# AC-Power-Monitor.net
KiCad netlist of a schematic drawn in Altium Designer
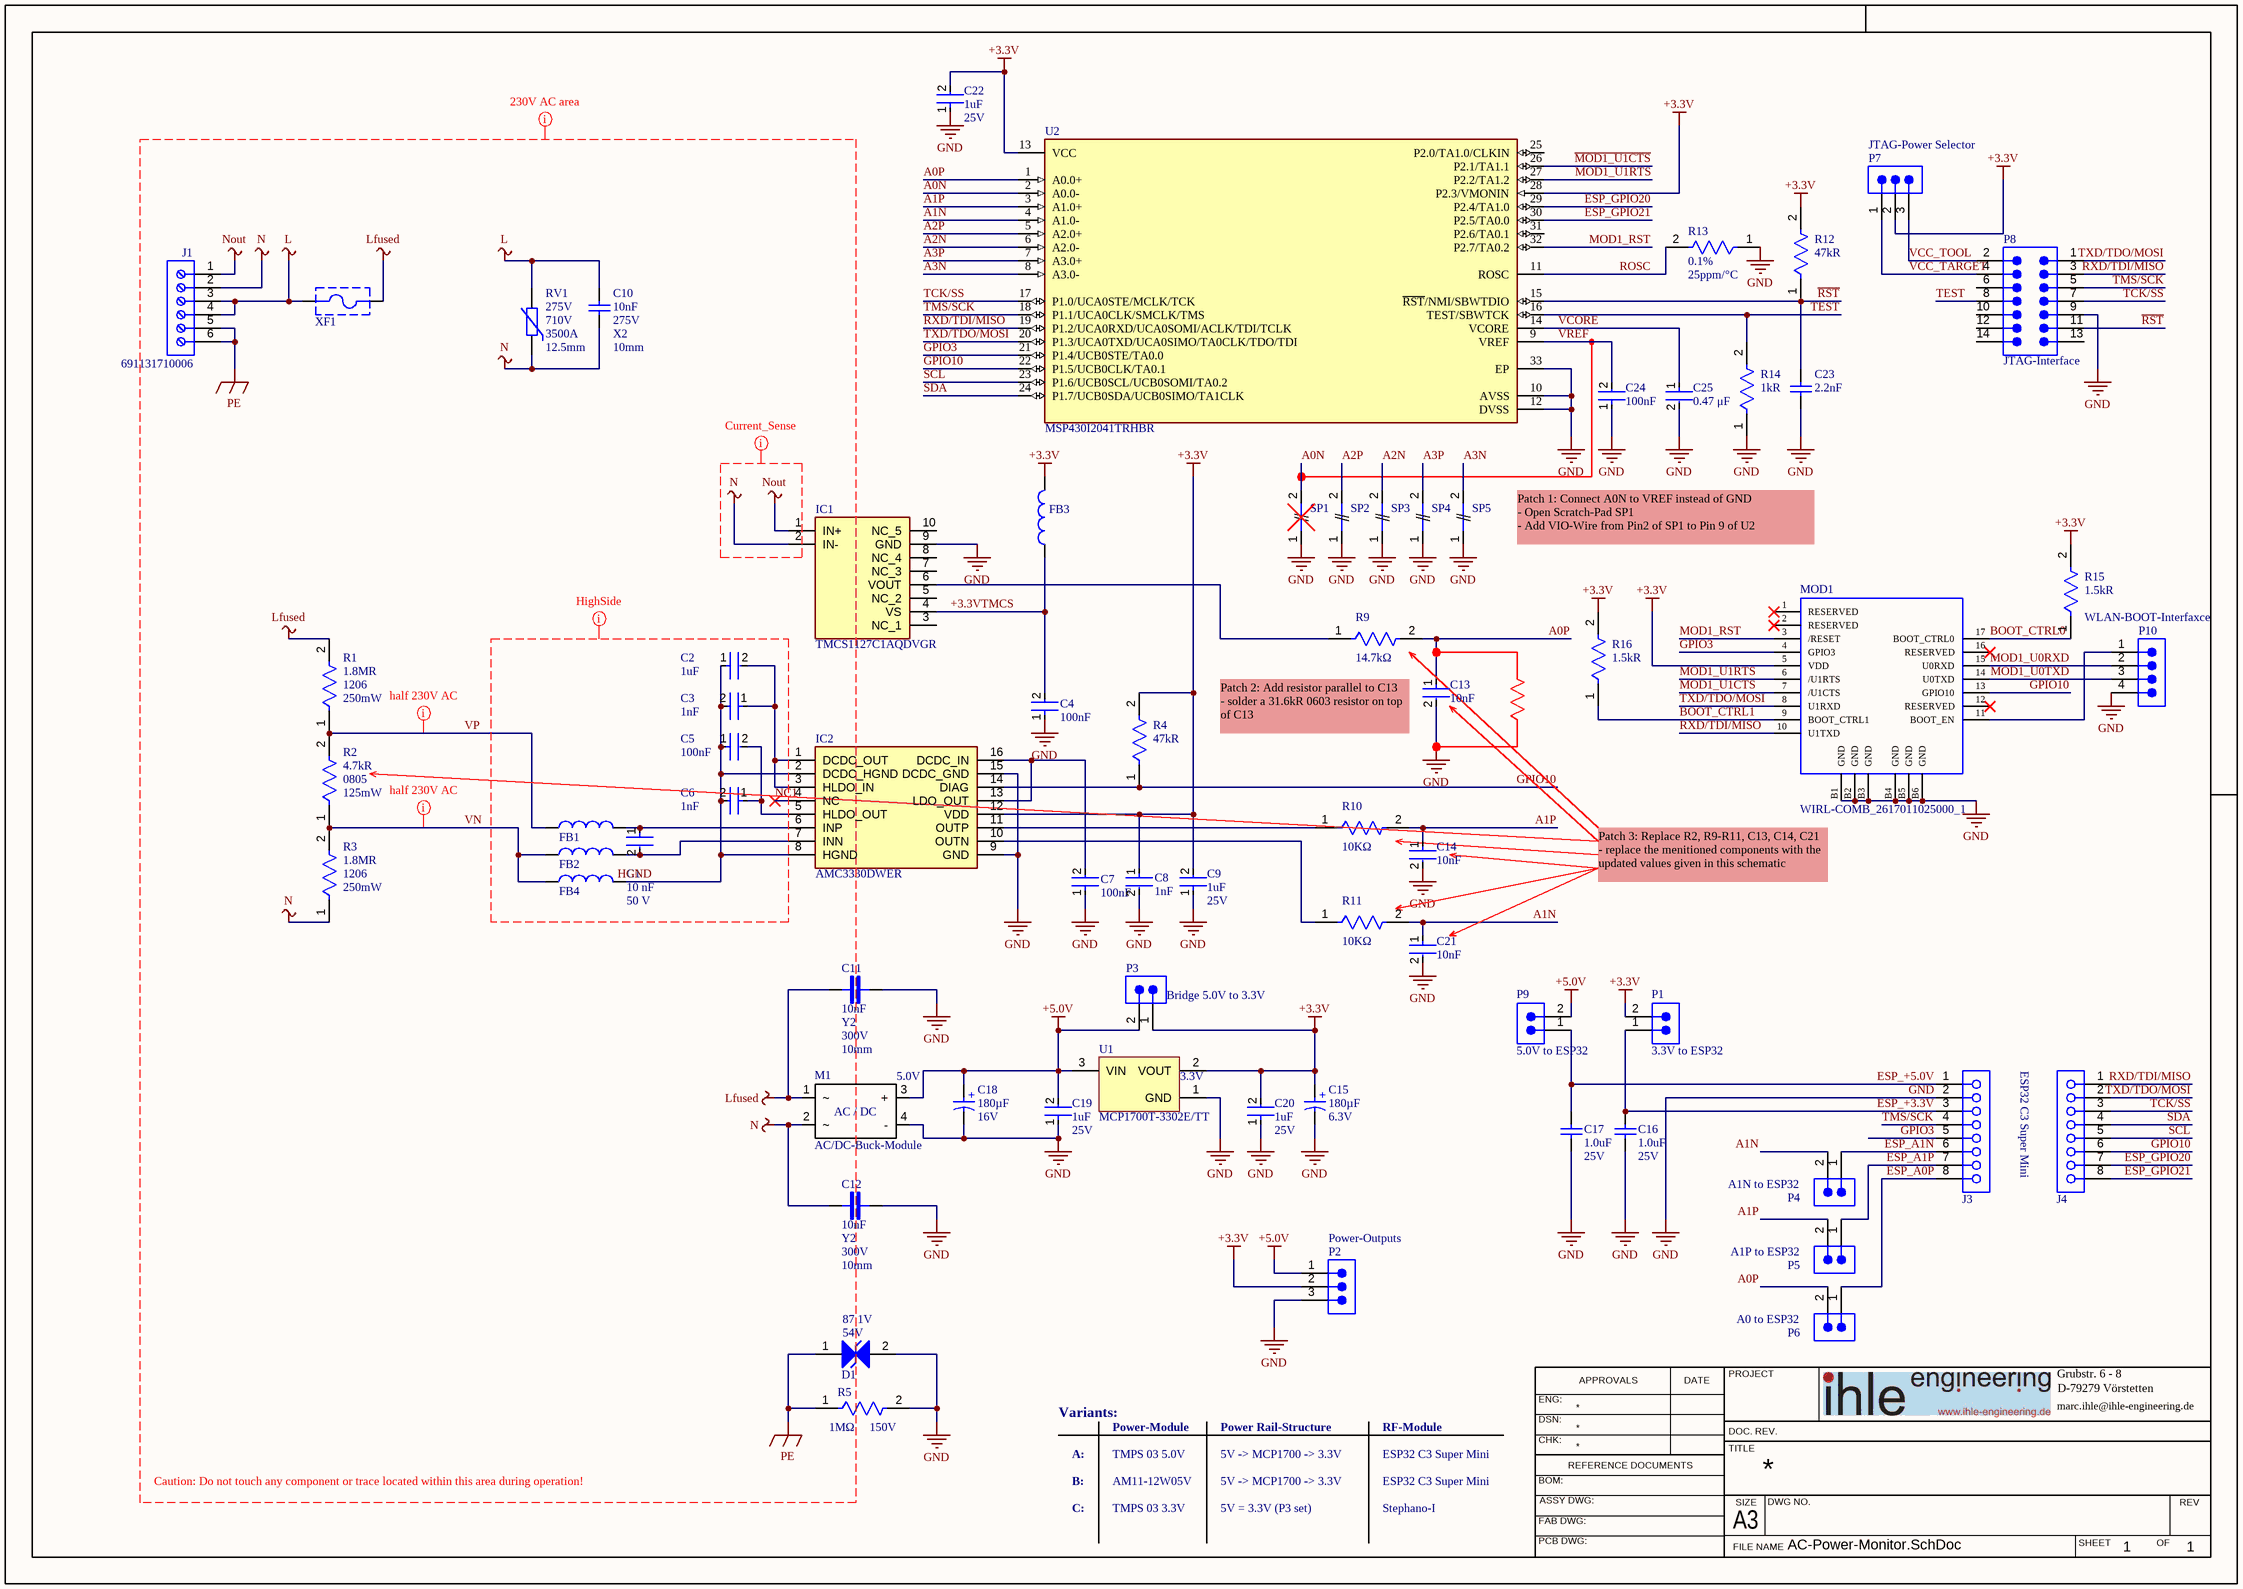
[diagram p0: AC-Power-Monitor.SchDoc]

(export (version "E")
  (design (tool "Eeschema 10.0.6"))
  (components
    (comp (ref "C1")
      (value "10 nF")
      (footprint "FP-CC0603-DA-MFG")
      (description "CAP CER 10000PF 50V X7R 0603")
      (fields
        (field (name "TOLERANCE") "0.1")
        (field (name "VOLTAGE RATING") "50 V")
        (field (name "MANUFACTURER PART NUMBER") "CC0603KRX7R9BB103")
      )
      (libsource (lib "Altium Content Vault") (part "11868f565c42a9108669ba33697ecf6"))
    )
    (comp (ref "C2")
      (value "CGA3E1X7R1E105K080AC")
      (footprint "FP-CGA3E-0_3-0_1-IPC_B")
      (description "Cap Ceramic 1uF 25V X7R 10% Pad SMD 0603 +125°C Automotive T/R")
      (fields
        (field (name "CAPACITANCE") "1uF")
        (field (name "VOLTAGE") "25V")
        (field (name "TOLERANCE") "10%")
      )
      (libsource (lib "Altium Content Vault") (part "b4654b650e69147ec39a6b967a45e02"))
    )
    (comp (ref "C3")
      (value "06035C102KAT2A")
      (footprint "FP-0603-L_1_6_0_15-W_0_81-IPC_B")
      (description "General Purpose Ceramic Capacitor, 0603, 1nF, 10%, X7R, 15%, 50V")
      (fields
        (field (name "CAPACITANCE") "1nF")
        (field (name "VOLTAGE") "50V")
        (field (name "TOLERANCE") "10%")
      )
      (libsource (lib "Altium Content Vault") (part "02cd4be3c70576c341d710602a673aa"))
    )
    (comp (ref "C4")
      (value "CGA3E2X7R1H104K080AA")
      (footprint "FP-CGA3E-0_3-0_1-IPC_A")
      (description "Cap Ceramic 100nF 50V X7R 10% Pad SMD 0603 +125°C Automotive T/R")
      (fields
        (field (name "TOLERANCE") "10%")
        (field (name "CAPACITANCE") "100nF")
        (field (name "VOLTAGE") "50V")
      )
      (libsource (lib "Altium Content Vault") (part "b4654b650e69147ec39a6b967a45e02"))
    )
    (comp (ref "C5")
      (value "CGA3E2X7R1H104K080AA")
      (footprint "FP-CGA3E-0_3-0_1-IPC_C")
      (description "Cap Ceramic 100nF 50V X7R 10% Pad SMD 0603 +125°C Automotive T/R")
      (fields
        (field (name "TOLERANCE") "10%")
        (field (name "CAPACITANCE") "100nF")
        (field (name "VOLTAGE") "50V")
      )
      (libsource (lib "Altium Content Vault") (part "b4654b650e69147ec39a6b967a45e02"))
    )
    (comp (ref "C6")
      (value "06035C102KAT2A")
      (footprint "FP-0603-L_1_6_0_15-W_0_81-IPC_B")
      (description "General Purpose Ceramic Capacitor, 0603, 1nF, 10%, X7R, 15%, 50V")
      (fields
        (field (name "CAPACITANCE") "1nF")
        (field (name "VOLTAGE") "50V")
        (field (name "TOLERANCE") "10%")
      )
      (libsource (lib "Altium Content Vault") (part "02cd4be3c70576c341d710602a673aa"))
    )
    (comp (ref "C7")
      (value "CGA3E2X7R1H104K080AA")
      (footprint "FP-CGA3E-0_3-0_1-IPC_A")
      (description "Cap Ceramic 100nF 50V X7R 10% Pad SMD 0603 +125°C Automotive T/R")
      (fields
        (field (name "TOLERANCE") "10%")
        (field (name "CAPACITANCE") "100nF")
        (field (name "VOLTAGE") "50V")
      )
      (libsource (lib "Altium Content Vault") (part "b4654b650e69147ec39a6b967a45e02"))
    )
    (comp (ref "C8")
      (value "06035C102KAT2A")
      (footprint "FP-0603-L_1_6_0_15-W_0_81-IPC_A")
      (description "General Purpose Ceramic Capacitor, 0603, 1nF, 10%, X7R, 15%, 50V")
      (fields
        (field (name "CAPACITANCE") "1nF")
        (field (name "VOLTAGE") "50V")
        (field (name "TOLERANCE") "10%")
      )
      (libsource (lib "Altium Content Vault") (part "02cd4be3c70576c341d710602a673aa"))
    )
    (comp (ref "C9")
      (value "CGA3E1X7R1E105K080AC")
      (footprint "FP-CGA3E-0_3-0_1-IPC_A")
      (description "Cap Ceramic 1uF 25V X7R 10% Pad SMD 0603 +125°C Automotive T/R")
      (fields
        (field (name "CAPACITANCE") "1uF")
        (field (name "VOLTAGE RATING") "25V")
        (field (name "VOLTAGE") "25V")
        (field (name "TOLERANCE") "10%")
      )
      (libsource (lib "Altium Content Vault") (part "b4654b650e69147ec39a6b967a45e02"))
    )
    (comp (ref "C10")
      (value "10nF")
      (footprint "WCAP-FTX2_L13W5H11_CS")
      (description "WCAP-FTX2 Film Capacitor, THT, L13 x W5 x H11mm, 10nF, 275V")
      (fields
        (field (name "MANUFACTURER PART NUMBER") "890324023006CS")
        (field (name "MANUFACTURER") "Wurth Elektronik")
        (field (name "CAPACITANCE") "10nF")
        (field (name "PITCH") "10mm")
        (field (name "RATED VOLTAGE (AC)") "275V")
        (field (name "SAFTY CLASS") "X2")
      )
      (libsource (lib "Altium_WCAP-FTX2 (rev23a)") (part "890324023006CS"))
    )
    (comp (ref "C11")
      (value "MKY22W21003I00")
      (footprint "MKY22W2")
      (fields
        (field (name "CAPACITANCE") "10nF")
        (field (name "SAFTY CLASS") "Y2")
        (field (name "VOLTAGE (AC)") "300V")
        (field (name "PITCH") "10mm")
      )
      (libsource (lib "Ihle_Components") (part "C_unipolar"))
    )
    (comp (ref "C12")
      (value "MKY22W21003I00")
      (footprint "MKY22W2")
      (fields
        (field (name "CAPACITANCE") "10nF")
        (field (name "SAFTY CLASS") "Y2")
        (field (name "VOLTAGE (AC)") "300V")
        (field (name "PITCH") "10mm")
      )
      (libsource (lib "Ihle_Components") (part "C_unipolar"))
    )
    (comp (ref "C13")
      (value "06035C103KAT4A")
      (footprint "FP-0603-L_1_6_0_15-W_0_81-IPC_B")
      (description "CAP CER 10000PF 50V X7R 0603")
      (fields
        (field (name "TOLERANCE") "10%")
        (field (name "VOLTAGE") "50V")
        (field (name "CAPACITANCE") "10nF")
      )
      (libsource (lib "Altium Content Vault") (part "02cd4be3c70576c341d710602a673aa"))
    )
    (comp (ref "C14")
      (value "06035C103KAT4A")
      (footprint "FP-0603-L_1_6_0_15-W_0_81-IPC_B")
      (description "CAP CER 10000PF 50V X7R 0603")
      (fields
        (field (name "TOLERANCE") "10%")
        (field (name "VOLTAGE") "50V")
        (field (name "CAPACITANCE") "10nF")
      )
      (libsource (lib "Altium Content Vault") (part "02cd4be3c70576c341d710602a673aa"))
    )
    (comp (ref "C15")
      (value "180µF")
      (footprint "WCAP-PSLC_D8H11.7")
      (description "WCAP-PSLC Aluminum Polymer Capacitor, V-Chip SMT, D8 x H11.7mm, 180µF, 6.3V")
      (fields
        (field (name "MANUFACTURER PART NUMBER") "875075155001")
        (field (name "MANUFACTURER") "Wurth Elektronik")
        (field (name "CAPACITANCE") "180µF")
        (field (name "RATED VOLTAGE (DC)") "6.3V")
      )
      (libsource (lib "Altium_WCAP-PSLC (rev22c)(1)") (part "875075155001"))
    )
    (comp (ref "C16")
      (value "C0603C105K3RACTU")
      (footprint "CAPC1608X87X35LL15T15")
      (fields
        (field (name "MANUFACTURER") "Kemet")
        (field (name "CAPACITANCE") "1.0uF")
        (field (name "RATED VOLTAGE") "25V")
      )
      (libsource (lib "Altium Content Vault") (part "CAP"))
    )
    (comp (ref "C17")
      (value "C0603C105K3RACTU")
      (footprint "CAPC1608X87X35LL15T15")
      (fields
        (field (name "MANUFACTURER") "Kemet")
        (field (name "CAPACITANCE") "1.0uF")
        (field (name "RATED VOLTAGE") "25V")
      )
      (libsource (lib "Altium Content Vault") (part "CAP"))
    )
    (comp (ref "C18")
      (value "180µF")
      (footprint "WCAP-PSLC_D8H11.7")
      (description "WCAP-PSLC Aluminum Polymer Capacitor, V-Chip SMT, D8 x H11.7mm, 180µF, 16V")
      (fields
        (field (name "MANUFACTURER PART NUMBER") "875075355001")
        (field (name "MANUFACTURER") "Wurth Elektronik")
        (field (name "CAPACITANCE") "180µF")
        (field (name "RATED VOLTAGE (DC)") "16V")
      )
      (libsource (lib "Altium_WCAP-PSLC (rev22c)(1)") (part "875075355001"))
    )
    (comp (ref "C19")
      (value "CGA3E1X7R1E105K080AC")
      (footprint "FP-CGA3E-0_3-0_1-IPC_A")
      (description "Cap Ceramic 1uF 25V X7R 10% Pad SMD 0603 +125°C Automotive T/R")
      (fields
        (field (name "CAPACITANCE") "1uF")
        (field (name "VOLTAGE RATING") "25V")
        (field (name "VOLTAGE") "25V")
        (field (name "TOLERANCE") "10%")
      )
      (libsource (lib "Altium Content Vault") (part "b4654b650e69147ec39a6b967a45e02"))
    )
    (comp (ref "C20")
      (value "CGA3E1X7R1E105K080AC")
      (footprint "FP-CGA3E-0_3-0_1-IPC_A")
      (description "Cap Ceramic 1uF 25V X7R 10% Pad SMD 0603 +125°C Automotive T/R")
      (fields
        (field (name "CAPACITANCE") "1uF")
        (field (name "VOLTAGE RATING") "25V")
        (field (name "VOLTAGE") "25V")
        (field (name "TOLERANCE") "10%")
      )
      (libsource (lib "Altium Content Vault") (part "b4654b650e69147ec39a6b967a45e02"))
    )
    (comp (ref "C21")
      (value "06035C103KAT4A")
      (footprint "FP-0603-L_1_6_0_15-W_0_81-IPC_B")
      (description "CAP CER 10000PF 50V X7R 0603")
      (fields
        (field (name "TOLERANCE") "10%")
        (field (name "VOLTAGE") "50V")
        (field (name "CAPACITANCE") "10nF")
      )
      (libsource (lib "Altium Content Vault") (part "02cd4be3c70576c341d710602a673aa"))
    )
    (comp (ref "C22")
      (value "CGA3E1X7R1E105K080AC")
      (footprint "FP-CGA3E-0_3-0_1-IPC_B")
      (description "Cap Ceramic 1uF 25V X7R 10% Pad SMD 0603 +125°C Automotive T/R")
      (fields
        (field (name "CAPACITANCE") "1uF")
        (field (name "VOLTAGE RATING") "25V")
        (field (name "VOLTAGE") "25V")
        (field (name "TOLERANCE") "10%")
      )
      (libsource (lib "Altium Content Vault") (part "b4654b650e69147ec39a6b967a45e02"))
    )
    (comp (ref "C23")
      (value "885012206085")
      (footprint "WCAP-CSGP_0603_L1.6W0.8H0.8_Reflow")
      (fields (field (name "CAPACITANCE") "2.2nF") (field (name "TOLERANCE") "10%"))
      (libsource (lib "Altium Content Vault") (part "Capacitor_Non-Polarized"))
    )
    (comp (ref "C24")
      (value "CGA3E2X7R1H104K080AA")
      (footprint "FP-CGA3E-0_3-0_1-IPC_B")
      (description "Cap Ceramic 100nF 50V X7R 10% Pad SMD 0603 +125°C Automotive T/R")
      (fields
        (field (name "TOLERANCE") "10%")
        (field (name "CAPACITANCE") "100nF")
        (field (name "VOLTAGE") "50V")
      )
      (libsource (lib "Altium Content Vault") (part "b4654b650e69147ec39a6b967a45e02"))
    )
    (comp (ref "C25")
      (value "0.47 μF")
      (footprint "FP-C0603C-CF-IPC_B")
      (description "CAP CER 0.47UF 16V X7R 0603")
      (fields (field (name "TOLERANCE") "0.1") (field (name "MANUFACTURER PART NUMBER") "C0603C474K4RACTU"))
      (libsource (lib "Altium Content Vault") (part "b4654b650e69147ec39a6b967a45e02"))
    )
    (comp (ref "D1")
      (value "400W, 54VDC")
      (footprint "WE-TVSP_DO-214AC_Bidirectional")
      (description "WE-TVSP SMT Power TVS Diode, DO-214AC, Bidirectional, 400W, 54VDC")
      (fields
        (field (name "MANUFACTURER PART NUMBER") "824501541")
        (field (name "MANUFACTURER") "Wurth Elektronik")
        (field (name "CLAMPING VOLTAGE") "87.1V")
        (field (name "OPERATING VOLTAGE (DC)") "54V")
      )
      (libsource (lib "Altium_WE-TVSP (rev22b)(1)") (part "824501541"))
    )
    (comp (ref "FB1")
      (value "1800Ohm")
      (footprint "WE-TMSB_0402_HF/HS/WB")
      (description "WE-TMSB Tiny Multilayer Suppression Bead, size 0402, 1800Ohm, 0.21A")
      (fields
        (field (name "MANUFACTURER PART NUMBER") "74269244182")
        (field (name "MANUFACTURER") "Wurth Elektronik")
      )
      (libsource (lib "WE-TMSB (rev24a)") (part "74269244182"))
    )
    (comp (ref "FB2")
      (value "1800Ohm")
      (footprint "WE-TMSB_0402_HF/HS/WB")
      (description "WE-TMSB Tiny Multilayer Suppression Bead, size 0402, 1800Ohm, 0.21A")
      (fields
        (field (name "MANUFACTURER PART NUMBER") "74269244182")
        (field (name "MANUFACTURER") "Wurth Elektronik")
      )
      (libsource (lib "WE-TMSB (rev24a)") (part "74269244182"))
    )
    (comp (ref "FB3")
      (value "1800Ohm")
      (footprint "WE-TMSB_0402_HF/HS/WB")
      (description "WE-TMSB Tiny Multilayer Suppression Bead, size 0402, 1800Ohm, 0.21A")
      (fields
        (field (name "MANUFACTURER PART NUMBER") "74269244182")
        (field (name "MANUFACTURER") "Wurth Elektronik")
      )
      (libsource (lib "WE-TMSB (rev24a)") (part "74269244182"))
    )
    (comp (ref "FB4")
      (value "1800Ohm")
      (footprint "WE-TMSB_0402_HF/HS/WB")
      (description "WE-TMSB Tiny Multilayer Suppression Bead, size 0402, 1800Ohm, 0.21A")
      (fields
        (field (name "MANUFACTURER PART NUMBER") "74269244182")
        (field (name "MANUFACTURER") "Wurth Elektronik")
      )
      (libsource (lib "WE-TMSB (rev24a)") (part "74269244182"))
    )
    (comp (ref "IC1")
      (value "TMCS1127C1AQDVGR")
      (footprint "SamacSys:TMCS1127C1AQDVGR")
      (description "Integrated Circuit")
      (libsource (lib "*") (part "TMCS1127C1AQDVGR"))
    )
    (comp (ref "IC2")
      (value "AMC3330DWER")
      (footprint "SamacSys:SOIC127P1030X265-16N")
      (description "Integrated Circuit")
      (fields (field (name "MOUSER PART NUMBER") "595-AMC3330DWER"))
      (libsource (lib "*") (part "AMC3330DWER"))
    )
    (comp (ref "J1")
      (value "691131710006")
      (footprint "691131710006")
      (description "WR-TBL Series 1317 Horizontal Entry, THT, pitch 5mm, 06p")
      (fields (field (name "MANUFACTURER") "Wurth Elektronik"))
      (libsource (lib "Altium_WR-TBL_Wire Protector (rev25a)") (part "691131710006"))
    )
    (comp (ref "J3")
      (value "61300811821")
      (footprint "61300811821")
      (description "WR-PHD Socket Header, THT, Vertical, pitch 2.54mm, 1 Row, 8P")
      (fields (field (name "MANUFACTURER") "Wurth Elektronik"))
      (libsource (lib "Altium_WR-PHD (rev24a)") (part "61300811821"))
    )
    (comp (ref "J4")
      (value "61300811821")
      (footprint "61300811821")
      (description "WR-PHD Socket Header, THT, Vertical, pitch 2.54mm, 1 Row, 8P")
      (fields (field (name "MANUFACTURER") "Wurth Elektronik"))
      (libsource (lib "Altium_WR-PHD (rev24a)") (part "61300811821"))
    )
    (comp (ref "M1")
      (value "AC/DC-Buck-Module")
      (footprint "TMPS 03")
      (fields (field (name "OUTPUT VOLTAGE") "5.0V"))
      (libsource (lib "Ihle_Components") (part "AC/DC-Buck-Module"))
    )
    (comp (ref "MOD1")
      (value "WIRL-COMB_2617011025000_1")
      (footprint "WE-FP-7")
      (description "Stephano-I - Combined 2.4 GHz Wi-Fi and Bluetooth® LE 5.0 Module")
      (fields (field (name "PART NUMBER") "2617011025000") (field (name "PUBLISHER") "Wurth Elektronik"))
      (libsource (lib "WE_WIRL_Rev17") (part "WIRL-COMB_2617011025000_1"))
    )
    (comp (ref "P1")
      (value "61300211121")
      (footprint "61300211121")
      (description "WR-PHD Pin Header, THT, Vertical, pitch 2.54mm, 1 Row, 2P")
      (fields (field (name "MANUFACTURER") "Wurth Elektronik") (field (name "PURPOSE") "3.3V to ESP32"))
      (libsource (lib "Altium_WR-PHD (rev24a)") (part "61300211121"))
    )
    (comp (ref "P2")
      (value "61300311121")
      (footprint "61300311121")
      (description "WR-PHD Pin Header, THT, Vertical, pitch 2.54mm, 1 Row, 3P")
      (fields (field (name "MANUFACTURER") "Wurth Elektronik") (field (name "PURPOSE") "Power-Outputs"))
      (libsource (lib "Altium_WR-PHD (rev24a)") (part "61300311121"))
    )
    (comp (ref "P3")
      (value "61300211121")
      (footprint "61300211121")
      (description "WR-PHD Pin Header, THT, Vertical, pitch 2.54mm, 1 Row, 2P")
      (fields (field (name "MANUFACTURER") "Wurth Elektronik") (field (name "PURPOSE") "Bridge 5.0V to 3.3V"))
      (libsource (lib "Altium_WR-PHD (rev24a)") (part "61300211121"))
    )
    (comp (ref "P4")
      (value "61300211121")
      (footprint "61300211121")
      (description "WR-PHD Pin Header, THT, Vertical, pitch 2.54mm, 1 Row, 2P")
      (fields (field (name "MANUFACTURER") "Wurth Elektronik") (field (name "PURPOSE") "A1N to ESP32"))
      (libsource (lib "Altium_WR-PHD (rev24a)") (part "61300211121"))
    )
    (comp (ref "P5")
      (value "61300211121")
      (footprint "61300211121")
      (description "WR-PHD Pin Header, THT, Vertical, pitch 2.54mm, 1 Row, 2P")
      (fields (field (name "MANUFACTURER") "Wurth Elektronik") (field (name "PURPOSE") "A1P to ESP32"))
      (libsource (lib "Altium_WR-PHD (rev24a)") (part "61300211121"))
    )
    (comp (ref "P6")
      (value "61300211121")
      (footprint "61300211121")
      (description "WR-PHD Pin Header, THT, Vertical, pitch 2.54mm, 1 Row, 2P")
      (fields (field (name "MANUFACTURER") "Wurth Elektronik") (field (name "PURPOSE") "A0 to ESP32"))
      (libsource (lib "Altium_WR-PHD (rev24a)") (part "61300211121"))
    )
    (comp (ref "P7")
      (value "61300311121")
      (footprint "61300311121")
      (description "WR-PHD Pin Header, THT, Vertical, pitch 2.54mm, 1 Row, 3P")
      (fields (field (name "MANUFACTURER") "Wurth Elektronik") (field (name "PURPOSE") "JTAG-Power Selector"))
      (libsource (lib "Altium_WR-PHD (rev24a)") (part "61300311121"))
    )
    (comp (ref "P8")
      (value "61301421121")
      (footprint "61301421121")
      (description "WR-PHD Pin Header, THT, Vertical, pitch 2.54mm, 2 Row, 14P")
      (fields (field (name "MANUFACTURER") "Wurth Elektronik") (field (name "PURPOSE") "JTAG-Interface"))
      (libsource (lib "Altium_WR-PHD (rev24a)") (part "61301421121"))
    )
    (comp (ref "P9")
      (value "61300211121")
      (footprint "61300211121")
      (description "WR-PHD Pin Header, THT, Vertical, pitch 2.54mm, 1 Row, 2P")
      (fields (field (name "MANUFACTURER") "Wurth Elektronik") (field (name "PURPOSE") "5.0V to ESP32"))
      (libsource (lib "Altium_WR-PHD (rev24a)") (part "61300211121"))
    )
    (comp (ref "P10")
      (value "61300411121")
      (footprint "61300411121")
      (description "WR-PHD Pin Header, THT, Vertical, pitch 2.54mm, 1 Row, 4P")
      (fields
        (field (name "MANUFACTURER") "Wurth Elektronik")
        (field (name "PURPOSE") "WLAN-BOOT-Interfaxce")
      )
      (libsource (lib "Altium_WR-PHD (rev24a)") (part "61300411121"))
    )
    (comp (ref "R1")
      (value "RK73H2BTTD1804F")
      (footprint "FP-RK73H2B-IPC_B")
      (description "1.8MΩ ±1% 0.25W Chip Resistor 1206 Thick Film AEC-Q200 Qualified")
      (fields
        (field (name "POWER RATING") "250mW")
        (field (name "CASE/PACKAGE") "1206")
        (field (name "RESISTANCE") "1.8MR")
        (field (name "TOLERANCE") "1%")
      )
      (libsource (lib "Altium Content Vault") (part "1029c3af85768c4190bb7ad29bc67b5"))
    )
    (comp (ref "R2")
      (value "CRCW08054K70FKEA")
      (footprint "FP-CRCW0805-e3-IPC_B")
      (description "RES Thick Film, 4.7kΩ, 1%, 0.125W, 100ppm/°C, 0805")
      (fields
        (field (name "CASE/PACKAGE") "0805")
        (field (name "MAX POWER DISSIPATION") "125mW")
        (field (name "RESISTANCE") "4.7kR")
        (field (name "TOLERANCE") "1%")
      )
      (libsource (lib "Altium Content Vault") (part "1029c3af85768c4190bb7ad29bc67b5"))
    )
    (comp (ref "R3")
      (value "RK73H2BTTD1804F")
      (footprint "FP-RK73H2B-IPC_B")
      (description "1.8MΩ ±1% 0.25W Chip Resistor 1206 Thick Film AEC-Q200 Qualified")
      (fields
        (field (name "POWER RATING") "250mW")
        (field (name "CASE/PACKAGE") "1206")
        (field (name "RESISTANCE") "1.8MR")
        (field (name "TOLERANCE") "1%")
      )
      (libsource (lib "Altium Content Vault") (part "1029c3af85768c4190bb7ad29bc67b5"))
    )
    (comp (ref "R4")
      (value "CRCW060347K0FKEA")
      (footprint "FP-CRCW0603-e3-IPC_B")
      (description "RES SMD 47K OHM 1% 1/10W 0603")
      (fields (field (name "TOLERANCE") "1%") (field (name "RESISTANCE") "47kR"))
      (libsource (lib "Altium Content Vault") (part "1029c3af85768c4190bb7ad29bc67b5"))
    )
    (comp (ref "R5")
      (value "1MΩ")
      (footprint "FP-CRGCQ0805-IPC_C")
      (description "CRGCQ0805 1MΩ 0.125W ±100ppm/°C 1% 150V")
      (fields
        (field (name "TOLERANCE") "0.01")
        (field (name "OCTOPART") "https://octopart.com/crgcq0805f1m0-te+connectivity-91018158")
        (field (name "VOLTAGE RATING") "150V")
      )
      (libsource (lib "Altium Content Vault") (part "1029c3af85768c4190bb7ad29bc67b5"))
    )
    (comp (ref "R9")
      (value "14.7kΩ")
      (footprint "FP-ERA3A-IPC_B")
      (description "14.7 kOhms ±0.1% 0.1W, 1/10W Chip Resistor 0603 (1608 Metric) Automotive AEC-Q200 Thin Film")
      (fields (field (name "OCTOPART") "https://octopart.com/era3aeb1472v-panasonic-42876006"))
      (libsource (lib "Altium Content Vault") (part "1029c3af85768c4190bb7ad29bc67b5"))
    )
    (comp (ref "R10")
      (value "10KΩ")
      (footprint "FP-RN731J-IPC_B")
      (description "Thin Film Resistors RN 0603 10KΩ 0.1% 10ppm/°C")
      (fields (field (name "MANUFACTURER") "TE Connectivity") (field (name "TOLERANCE") "0.1%"))
      (libsource (lib "Altium Content Vault") (part "1029c3af85768c4190bb7ad29bc67b5"))
    )
    (comp (ref "R11")
      (value "10KΩ")
      (footprint "FP-RN731J-IPC_B")
      (description "Thin Film Resistors RN 0603 10KΩ 0.1% 10ppm/°C")
      (fields (field (name "MANUFACTURER") "TE Connectivity") (field (name "TOLERANCE") "0.1%"))
      (libsource (lib "Altium Content Vault") (part "1029c3af85768c4190bb7ad29bc67b5"))
    )
    (comp (ref "R12")
      (value "KTR03EZPF4702")
      (footprint "FP-KTR03-IPC_C")
      (description "Res Thick Film 0603 47kΩ 1% 0.1W ±100ppm/°C Automotive Paper T/R")
      (fields (field (name "TOLERANCE") "1%") (field (name "RESISTANCE") "47kR"))
      (libsource (lib "Altium Content Vault") (part "1029c3af85768c4190bb7ad29bc67b5"))
    )
    (comp (ref "R13")
      (value "CPF0603B20KE1")
      (footprint "FP-CPF0603-MFG")
      (description "RES SMD 20KΩ 0.1% 1/16W 0603")
      (fields
        (field (name "MANUFACTURER") "TE Connectivity")
        (field (name "TOLERANCE") "0.1%")
        (field (name "TEMPERATURE COEFFICIENT") "25ppm/°C")
        (field (name "OCTOPART") "https://octopart.com/cpf0603b20ke1-te+connectivity-22738773")
      )
      (libsource (lib "Altium Content Vault") (part "1029c3af85768c4190bb7ad29bc67b5"))
    )
    (comp (ref "R14")
      (value "AC0603FR-071KL")
      (footprint "FP-AC0603-IPC_B")
      (description "RES 1kΩ 1.00% 0.1W 0603")
      (fields (field (name "TOLERANCE") "1%") (field (name "RESISTANCE") "1kR"))
      (libsource (lib "Altium Content Vault") (part "1029c3af85768c4190bb7ad29bc67b5"))
    )
    (comp (ref "R15")
      (value "CRCW06031K50FKEA")
      (footprint "FP-CRCW0603-e3-IPC_A")
      (description "RES Thick Film, 1.5kΩ, 1%, 0.1W, 100ppm/°C, 0603")
      (fields (field (name "RESISTANCE") "1.5kR") (field (name "TOLERANCE") "1%"))
      (libsource (lib "Altium Content Vault") (part "1029c3af85768c4190bb7ad29bc67b5"))
    )
    (comp (ref "R16")
      (value "CRCW06031K50FKEA")
      (footprint "FP-CRCW0603-e3-IPC_A")
      (description "RES Thick Film, 1.5kΩ, 1%, 0.1W, 100ppm/°C, 0603")
      (fields (field (name "RESISTANCE") "1.5kR") (field (name "TOLERANCE") "1%"))
      (libsource (lib "Altium Content Vault") (part "1029c3af85768c4190bb7ad29bc67b5"))
    )
    (comp (ref "RV1")
      (value "275VAC, 350VDC")
      (footprint "D12.5W6.5H16P1.3")
      (description "WE-VD Disk Varistor, THT, 275VAC, 350VDC, 190pF")
      (fields
        (field (name "MANUFACTURER PART NUMBER") "820412711")
        (field (name "MANUFACTURER") "Wurth Elektronik")
        (field (name "DIAMETER") "12.5mm")
        (field (name "CLAMPING VOLTAGE") "710V")
        (field (name "OPERATING VOLTAGE (AC)") "275V")
        (field (name "(REVERSE) PEAK PULSE CURRENT") "3500A")
      )
      (libsource (lib "Altium_WE-VD (rev23a)(2)") (part "820412711"))
    )
    (comp (ref "SP1")
      (value "Scratch_NetTie")
      (footprint "Scratch_NetTie_0603")
      (libsource (lib "Ihle_Components") (part "Scratch_NetTie"))
    )
    (comp (ref "SP2")
      (value "Scratch_NetTie")
      (footprint "Scratch_NetTie_0603")
      (libsource (lib "Ihle_Components") (part "Scratch_NetTie"))
    )
    (comp (ref "SP3")
      (value "Scratch_NetTie")
      (footprint "Scratch_NetTie_0603")
      (libsource (lib "Ihle_Components") (part "Scratch_NetTie"))
    )
    (comp (ref "SP4")
      (value "Scratch_NetTie")
      (footprint "Scratch_NetTie_0603")
      (libsource (lib "Ihle_Components") (part "Scratch_NetTie"))
    )
    (comp (ref "SP5")
      (value "Scratch_NetTie")
      (footprint "Scratch_NetTie_0603")
      (libsource (lib "Ihle_Components") (part "Scratch_NetTie"))
    )
    (comp (ref "U1")
      (value "MCP1700T-3302E/TT")
      (footprint "SOT-23-TT3_L")
      (description "Low Quiescent Current LDO, 3-Pin SOT-23, Extended Temperature, Tape and Reel")
      (fields (field (name "OUTPUT VOLTAGE") "3.3V"))
      (libsource (lib "Altium Content Vault") (part "PM-LINEREG-MCP1700-IL3"))
    )
    (comp (ref "U2")
      (value "MSP430I2041TRHBR")
      (footprint "FP-RHB0032M-MFG")
      (description "IC MCU 16BIT 32KB FLASH 32VQFN")
      (libsource (lib "Altium Content Vault") (part "14e932a678a7e56db3e91f6de8174c1"))
    )
    (comp (ref "XF1")
      (value "696106003002")
      (footprint "696106003002")
      (description "WR-FSH Fuseholder THT Blocks PCB Clip Cover")
      (fields (field (name "MANUFACTURER") "Wurth Elektronik"))
      (libsource (lib "Altium_WR-FSH (rev22a)(1)") (part "696106003002"))
    )
  )
  (nets
    (net (code "1") (name "+3.3V") (class "Default")
      (node (ref "C15") (pin "1") (pinfunction "P_1") (pintype "passive"))
      (node (ref "C20") (pin "2") (pinfunction "2_2") (pintype "passive"))
      (node (ref "C22") (pin "2") (pinfunction "2_2") (pintype "passive"))
      (node (ref "C8") (pin "1") (pinfunction "1_1") (pintype "passive"))
      (node (ref "C9") (pin "2") (pinfunction "2_2") (pintype "passive"))
      (node (ref "FB3") (pin "2") (pinfunction "2_2") (pintype "passive"))
      (node (ref "IC2") (pin "12") (pinfunction "VDD_12") (pintype "passive"))
      (node (ref "MOD1") (pin "5") (pinfunction "VDD_5") (pintype "passive"))
      (node (ref "P1") (pin "2") (pinfunction "2_2") (pintype "passive"))
      (node (ref "P2") (pin "2") (pinfunction "2_2") (pintype "passive"))
      (node (ref "P3") (pin "1") (pinfunction "1_1") (pintype "passive"))
      (node (ref "P7") (pin "2") (pinfunction "2_2") (pintype "passive"))
      (node (ref "R12") (pin "2") (pinfunction "2_2") (pintype "passive"))
      (node (ref "R15") (pin "2") (pinfunction "2_2") (pintype "passive"))
      (node (ref "R16") (pin "2") (pinfunction "2_2") (pintype "passive"))
      (node (ref "R4") (pin "2") (pinfunction "2_2") (pintype "passive"))
      (node (ref "U1") (pin "2") (pinfunction "VOUT_2") (pintype "power_in"))
      (node (ref "U2") (pin "13") (pinfunction "VCC_13") (pintype "power_in"))
      (node (ref "U2") (pin "28") (pinfunction "P2.3/VMONIN_28") (pintype "input"))
    )
    (net (code "2") (name "+5.0V") (class "Default")
      (node (ref "C18") (pin "1") (pinfunction "P_1") (pintype "passive"))
      (node (ref "C19") (pin "2") (pinfunction "2_2") (pintype "passive"))
      (node (ref "M1") (pin "3") (pinfunction "+_3") (pintype "passive"))
      (node (ref "P2") (pin "1") (pinfunction "1_1") (pintype "passive"))
      (node (ref "P3") (pin "2") (pinfunction "2_2") (pintype "passive"))
      (node (ref "P9") (pin "2") (pinfunction "2_2") (pintype "passive"))
      (node (ref "U1") (pin "3") (pinfunction "VIN_3") (pintype "power_in"))
    )
    (net (code "3") (name "/+3.3VTMCS") (class "Default")
      (node (ref "C4") (pin "2") (pinfunction "2_2") (pintype "passive"))
      (node (ref "FB3") (pin "1") (pinfunction "1_1") (pintype "passive"))
      (node (ref "IC1") (pin "4") (pinfunction "VS_4") (pintype "passive"))
    )
    (net (code "4") (name "/A0N") (class "Default")
      (node (ref "SP1") (pin "2") (pinfunction "136_2") (pintype "passive"))
      (node (ref "U2") (pin "2") (pinfunction "A0.0-_2") (pintype "input"))
    )
    (net (code "5") (name "/A0P") (class "Default")
      (node (ref "C13") (pin "1") (pinfunction "1_1") (pintype "passive"))
      (node (ref "P6") (pin "2") (pinfunction "2_2") (pintype "passive"))
      (node (ref "R9") (pin "2") (pinfunction "2_2") (pintype "passive"))
      (node (ref "U2") (pin "1") (pinfunction "A0.0+_1") (pintype "input"))
    )
    (net (code "6") (name "/A1N") (class "Default")
      (node (ref "C21") (pin "1") (pinfunction "1_1") (pintype "passive"))
      (node (ref "P4") (pin "2") (pinfunction "2_2") (pintype "passive"))
      (node (ref "R11") (pin "2") (pinfunction "2_2") (pintype "passive"))
      (node (ref "U2") (pin "4") (pinfunction "A1.0-_4") (pintype "input"))
    )
    (net (code "7") (name "/A1P") (class "Default")
      (node (ref "C14") (pin "1") (pinfunction "1_1") (pintype "passive"))
      (node (ref "P5") (pin "2") (pinfunction "2_2") (pintype "passive"))
      (node (ref "R10") (pin "2") (pinfunction "2_2") (pintype "passive"))
      (node (ref "U2") (pin "3") (pinfunction "A1.0+_3") (pintype "input"))
    )
    (net (code "8") (name "/A2N") (class "Default")
      (node (ref "SP3") (pin "2") (pinfunction "136_2") (pintype "passive"))
      (node (ref "U2") (pin "6") (pinfunction "A2.0-_6") (pintype "input"))
    )
    (net (code "9") (name "/A2P") (class "Default")
      (node (ref "SP2") (pin "2") (pinfunction "136_2") (pintype "passive"))
      (node (ref "U2") (pin "5") (pinfunction "A2.0+_5") (pintype "input"))
    )
    (net (code "10") (name "/A3N") (class "Default")
      (node (ref "SP5") (pin "2") (pinfunction "136_2") (pintype "passive"))
      (node (ref "U2") (pin "8") (pinfunction "A3.0-_8") (pintype "input"))
    )
    (net (code "11") (name "/A3P") (class "Default")
      (node (ref "SP4") (pin "2") (pinfunction "136_2") (pintype "passive"))
      (node (ref "U2") (pin "7") (pinfunction "A3.0+_7") (pintype "input"))
    )
    (net (code "12") (name "/BOOT_CTRL0") (class "Default")
      (node (ref "MOD1") (pin "17") (pinfunction "BOOT_CTRL0_17") (pintype "passive"))
      (node (ref "R15") (pin "1") (pinfunction "1_1") (pintype "passive"))
    )
    (net (code "13") (name "/BOOT_CTRL1") (class "Default")
      (node (ref "MOD1") (pin "9") (pinfunction "BOOT_CTRL1_9") (pintype "passive"))
      (node (ref "R16") (pin "1") (pinfunction "1_1") (pintype "passive"))
    )
    (net (code "14") (name "/ESP_+3.3V") (class "Default")
      (node (ref "C16") (pin "2") (pinfunction "2_2") (pintype "passive"))
      (node (ref "J3") (pin "3") (pinfunction "3_3") (pintype "passive"))
      (node (ref "P1") (pin "1") (pinfunction "1_1") (pintype "passive"))
    )
    (net (code "15") (name "/ESP_+5.0V") (class "Default")
      (node (ref "C17") (pin "2") (pinfunction "2_2") (pintype "passive"))
      (node (ref "J3") (pin "1") (pinfunction "1_1") (pintype "passive"))
      (node (ref "P9") (pin "1") (pinfunction "1_1") (pintype "passive"))
    )
    (net (code "16") (name "/ESP_A0P") (class "Default")
      (node (ref "J3") (pin "8") (pinfunction "8_8") (pintype "passive"))
      (node (ref "P6") (pin "1") (pinfunction "1_1") (pintype "passive"))
    )
    (net (code "17") (name "/ESP_A1N") (class "Default")
      (node (ref "J3") (pin "6") (pinfunction "6_6") (pintype "passive"))
      (node (ref "P4") (pin "1") (pinfunction "1_1") (pintype "passive"))
    )
    (net (code "18") (name "/ESP_A1P") (class "Default")
      (node (ref "J3") (pin "7") (pinfunction "7_7") (pintype "passive"))
      (node (ref "P5") (pin "1") (pinfunction "1_1") (pintype "passive"))
    )
    (net (code "19") (name "/ESP_GPIO20") (class "Default")
      (node (ref "J4") (pin "7") (pinfunction "7_7") (pintype "passive"))
      (node (ref "U2") (pin "29") (pinfunction "P2.4/TA1.0_29") (pintype "bidirectional"))
    )
    (net (code "20") (name "/ESP_GPIO21") (class "Default")
      (node (ref "J4") (pin "8") (pinfunction "8_8") (pintype "passive"))
      (node (ref "U2") (pin "30") (pinfunction "P2.5/TA0.0_30") (pintype "bidirectional"))
    )
    (net (code "21") (name "/GPIO3") (class "Default")
      (node (ref "J3") (pin "5") (pinfunction "5_5") (pintype "passive"))
      (node (ref "MOD1") (pin "4") (pinfunction "GPIO3_4") (pintype "passive"))
      (node (ref "U2") (pin "21") (pinfunction "P1.4/UCB0STE/TA0.0_21") (pintype "bidirectional"))
    )
    (net (code "22") (name "/GPIO10") (class "Default")
      (node (ref "IC2") (pin "14") (pinfunction "DIAG_14") (pintype "passive"))
      (node (ref "J4") (pin "6") (pinfunction "6_6") (pintype "passive"))
      (node (ref "MOD1") (pin "13") (pinfunction "GPIO10_13") (pintype "passive"))
      (node (ref "R4") (pin "1") (pinfunction "1_1") (pintype "passive"))
      (node (ref "U2") (pin "22") (pinfunction "P1.5/UCB0CLK/TA0.1_22") (pintype "bidirectional"))
    )
    (net (code "23") (name "/HGND") (class "Default")
      (node (ref "C2") (pin "1") (pinfunction "1_1") (pintype "passive"))
      (node (ref "C3") (pin "2") (pinfunction "2_2") (pintype "passive"))
      (node (ref "C5") (pin "1") (pinfunction "1_1") (pintype "passive"))
      (node (ref "C6") (pin "2") (pinfunction "2_2") (pintype "passive"))
      (node (ref "FB4") (pin "2") (pinfunction "2_2") (pintype "passive"))
      (node (ref "IC2") (pin "2") (pinfunction "DCDC_HGND_2") (pintype "passive"))
      (node (ref "IC2") (pin "8") (pinfunction "HGND_8") (pintype "passive"))
    )
    (net (code "24") (name "/MOD1_RST") (class "Default")
      (node (ref "MOD1") (pin "3") (pinfunction "/RESET_3") (pintype "passive"))
      (node (ref "U2") (pin "32") (pinfunction "P2.7/TA0.2_32") (pintype "bidirectional"))
    )
    (net (code "25") (name "/MOD1_U0RXD") (class "Default")
      (node (ref "MOD1") (pin "15") (pinfunction "U0RXD_15") (pintype "passive"))
      (node (ref "P10") (pin "2") (pinfunction "2_2") (pintype "passive"))
    )
    (net (code "26") (name "/MOD1_U0TXD") (class "Default")
      (node (ref "MOD1") (pin "14") (pinfunction "U0TXD_14") (pintype "passive"))
      (node (ref "P10") (pin "3") (pinfunction "3_3") (pintype "passive"))
    )
    (net (code "27") (name "/MOD1_U1CTS") (class "Default")
      (node (ref "MOD1") (pin "7") (pinfunction "/U1CTS_7") (pintype "passive"))
      (node (ref "U2") (pin "26") (pinfunction "P2.1/TA1.1_26") (pintype "bidirectional"))
    )
    (net (code "28") (name "/MOD1_U1RTS") (class "Default")
      (node (ref "MOD1") (pin "6") (pinfunction "/U1RTS_6") (pintype "passive"))
      (node (ref "U2") (pin "27") (pinfunction "P2.2/TA1.2_27") (pintype "bidirectional"))
    )
    (net (code "29") (name "/NC1") (class "Default")
      (node (ref "IC2") (pin "4") (pinfunction "NC_4") (pintype "passive+no_connect"))
    )
    (net (code "30") (name "/ROSC") (class "Default")
      (node (ref "R13") (pin "2") (pinfunction "2_2") (pintype "passive"))
      (node (ref "U2") (pin "11") (pinfunction "ROSC_11") (pintype "passive"))
    )
    (net (code "31") (name "/RST") (class "Default")
      (node (ref "C23") (pin "2") (pinfunction "2_2") (pintype "passive"))
      (node (ref "P8") (pin "11") (pinfunction "11_11") (pintype "passive"))
      (node (ref "R12") (pin "1") (pinfunction "1_1") (pintype "passive"))
      (node (ref "U2") (pin "15") (pinfunction "~{RST}/NMI/SBWTDIO_15") (pintype "bidirectional"))
    )
    (net (code "32") (name "/RXD{slash}TDI{slash}MISO") (class "Default")
      (node (ref "J4") (pin "1") (pinfunction "1_1") (pintype "passive"))
      (node (ref "MOD1") (pin "10") (pinfunction "U1TXD_10") (pintype "passive"))
      (node (ref "P8") (pin "3") (pinfunction "3_3") (pintype "passive"))
      (node (ref "U2") (pin "19") (pinfunction "P1.2/UCA0RXD/UCA0SOMI/ACLK/TDI/TCLK_19") (pintype "bidirectional"))
    )
    (net (code "33") (name "/SCL") (class "Default")
      (node (ref "J4") (pin "5") (pinfunction "5_5") (pintype "passive"))
      (node (ref "U2") (pin "23") (pinfunction "P1.6/UCB0SCL/UCB0SOMI/TA0.2_23") (pintype "bidirectional"))
    )
    (net (code "34") (name "/SDA") (class "Default")
      (node (ref "J4") (pin "4") (pinfunction "4_4") (pintype "passive"))
      (node (ref "U2") (pin "24") (pinfunction "P1.7/UCB0SDA/UCB0SIMO/TA1CLK_24") (pintype "bidirectional"))
    )
    (net (code "35") (name "/TCK{slash}SS") (class "Default")
      (node (ref "J4") (pin "3") (pinfunction "3_3") (pintype "passive"))
      (node (ref "P8") (pin "7") (pinfunction "7_7") (pintype "passive"))
      (node (ref "U2") (pin "17") (pinfunction "P1.0/UCA0STE/MCLK/TCK_17") (pintype "bidirectional"))
    )
    (net (code "36") (name "/TEST") (class "Default")
      (node (ref "P8") (pin "8") (pinfunction "8_8") (pintype "passive"))
      (node (ref "R14") (pin "2") (pinfunction "2_2") (pintype "passive"))
      (node (ref "U2") (pin "16") (pinfunction "TEST/SBWTCK_16") (pintype "bidirectional"))
    )
    (net (code "37") (name "/TMS{slash}SCK") (class "Default")
      (node (ref "J3") (pin "4") (pinfunction "4_4") (pintype "passive"))
      (node (ref "P8") (pin "5") (pinfunction "5_5") (pintype "passive"))
      (node (ref "U2") (pin "18") (pinfunction "P1.1/UCA0CLK/SMCLK/TMS_18") (pintype "bidirectional"))
    )
    (net (code "38") (name "/TXD{slash}TDO{slash}MOSI") (class "Default")
      (node (ref "J4") (pin "2") (pinfunction "2_2") (pintype "passive"))
      (node (ref "MOD1") (pin "8") (pinfunction "U1RXD_8") (pintype "passive"))
      (node (ref "P8") (pin "1") (pinfunction "1_1") (pintype "passive"))
      (node (ref "U2") (pin "20") (pinfunction "P1.3/UCA0TXD/UCA0SIMO/TA0CLK/TDO/TDI_20") (pintype "bidirectional"))
    )
    (net (code "39") (name "/VCC_TARGET") (class "Default")
      (node (ref "P7") (pin "1") (pinfunction "1_1") (pintype "passive"))
      (node (ref "P8") (pin "4") (pinfunction "4_4") (pintype "passive"))
    )
    (net (code "40") (name "/VCC_TOOL") (class "Default")
      (node (ref "P7") (pin "3") (pinfunction "3_3") (pintype "passive"))
      (node (ref "P8") (pin "2") (pinfunction "2_2") (pintype "passive"))
    )
    (net (code "41") (name "/VCORE") (class "Default")
      (node (ref "C25") (pin "1") (pinfunction "1_1") (pintype "passive"))
      (node (ref "U2") (pin "14") (pinfunction "VCORE_14") (pintype "passive"))
    )
    (net (code "42") (name "/VN") (class "Default")
      (node (ref "FB2") (pin "1") (pinfunction "1_1") (pintype "passive"))
      (node (ref "FB4") (pin "1") (pinfunction "1_1") (pintype "passive"))
      (node (ref "R2") (pin "1") (pinfunction "1_1") (pintype "passive"))
      (node (ref "R3") (pin "2") (pinfunction "2_2") (pintype "passive"))
    )
    (net (code "43") (name "/VP") (class "Default")
      (node (ref "FB1") (pin "1") (pinfunction "1_1") (pintype "passive"))
      (node (ref "R1") (pin "1") (pinfunction "1_1") (pintype "passive"))
      (node (ref "R2") (pin "2") (pinfunction "2_2") (pintype "passive"))
    )
    (net (code "44") (name "/VREF") (class "Default")
      (node (ref "C24") (pin "2") (pinfunction "2_2") (pintype "passive"))
      (node (ref "U2") (pin "9") (pinfunction "VREF_9") (pintype "power_in"))
    )
    (net (code "45") (name "GND") (class "Default")
      (node (ref "C11") (pin "2") (pinfunction "2_2") (pintype "passive"))
      (node (ref "C12") (pin "2") (pinfunction "2_2") (pintype "passive"))
      (node (ref "C13") (pin "2") (pinfunction "2_2") (pintype "passive"))
      (node (ref "C14") (pin "2") (pinfunction "2_2") (pintype "passive"))
      (node (ref "C15") (pin "2") (pinfunction "N_2") (pintype "passive"))
      (node (ref "C16") (pin "1") (pinfunction "1_1") (pintype "passive"))
      (node (ref "C17") (pin "1") (pinfunction "1_1") (pintype "passive"))
      (node (ref "C18") (pin "2") (pinfunction "N_2") (pintype "passive"))
      (node (ref "C19") (pin "1") (pinfunction "1_1") (pintype "passive"))
      (node (ref "C20") (pin "1") (pinfunction "1_1") (pintype "passive"))
      (node (ref "C21") (pin "2") (pinfunction "2_2") (pintype "passive"))
      (node (ref "C22") (pin "1") (pinfunction "1_1") (pintype "passive"))
      (node (ref "C23") (pin "1") (pinfunction "1_1") (pintype "passive"))
      (node (ref "C24") (pin "1") (pinfunction "1_1") (pintype "passive"))
      (node (ref "C25") (pin "2") (pinfunction "2_2") (pintype "passive"))
      (node (ref "C4") (pin "1") (pinfunction "1_1") (pintype "passive"))
      (node (ref "C7") (pin "1") (pinfunction "1_1") (pintype "passive"))
      (node (ref "C8") (pin "2") (pinfunction "2_2") (pintype "passive"))
      (node (ref "C9") (pin "1") (pinfunction "1_1") (pintype "passive"))
      (node (ref "D1") (pin "2") (pinfunction "2_2") (pintype "passive"))
      (node (ref "IC1") (pin "9") (pinfunction "GND_9") (pintype "passive"))
      (node (ref "IC2") (pin "15") (pinfunction "DCDC_GND_15") (pintype "passive"))
      (node (ref "IC2") (pin "9") (pinfunction "GND_9") (pintype "passive"))
      (node (ref "J3") (pin "2") (pinfunction "2_2") (pintype "passive"))
      (node (ref "M1") (pin "4") (pinfunction "-_4") (pintype "passive"))
      (node (ref "MOD1") (pin "B1") (pinfunction "GND_B1") (pintype "passive"))
      (node (ref "MOD1") (pin "B2") (pinfunction "GND_B2") (pintype "passive"))
      (node (ref "MOD1") (pin "B3") (pinfunction "GND_B3") (pintype "passive"))
      (node (ref "MOD1") (pin "B4") (pinfunction "GND_B4") (pintype "passive"))
      (node (ref "MOD1") (pin "B5") (pinfunction "GND_B5") (pintype "passive"))
      (node (ref "MOD1") (pin "B6") (pinfunction "GND_B6") (pintype "passive"))
      (node (ref "P10") (pin "4") (pinfunction "4_4") (pintype "passive"))
      (node (ref "P2") (pin "3") (pinfunction "3_3") (pintype "passive"))
      (node (ref "P8") (pin "9") (pinfunction "9_9") (pintype "passive"))
      (node (ref "R13") (pin "1") (pinfunction "1_1") (pintype "passive"))
      (node (ref "R14") (pin "1") (pinfunction "1_1") (pintype "passive"))
      (node (ref "R5") (pin "2") (pinfunction "2_2") (pintype "passive"))
      (node (ref "SP1") (pin "1") (pinfunction "137_1") (pintype "passive"))
      (node (ref "SP2") (pin "1") (pinfunction "137_1") (pintype "passive"))
      (node (ref "SP3") (pin "1") (pinfunction "137_1") (pintype "passive"))
      (node (ref "SP4") (pin "1") (pinfunction "137_1") (pintype "passive"))
      (node (ref "SP5") (pin "1") (pinfunction "137_1") (pintype "passive"))
      (node (ref "U1") (pin "1") (pinfunction "GND_1") (pintype "power_in"))
      (node (ref "U2") (pin "10") (pinfunction "AVSS_10") (pintype "power_in"))
      (node (ref "U2") (pin "12") (pinfunction "DVSS_12") (pintype "power_in"))
      (node (ref "U2") (pin "33") (pinfunction "EP_33") (pintype "passive"))
    )
    (net (code "46") (name "L") (class "Default")
      (node (ref "C10") (pin "2") (pinfunction "2_2") (pintype "passive"))
      (node (ref "J1") (pin "3") (pinfunction "3_3") (pintype "passive"))
      (node (ref "J1") (pin "4") (pinfunction "4_4") (pintype "passive"))
      (node (ref "RV1") (pin "2") (pinfunction "2_2") (pintype "passive"))
      (node (ref "XF1") (pin "1") (pinfunction "1_1") (pintype "passive"))
    )
    (net (code "47") (name "Lfused") (class "Default")
      (node (ref "C11") (pin "1") (pinfunction "1_1") (pintype "passive"))
      (node (ref "M1") (pin "1") (pinfunction "~_1") (pintype "passive"))
      (node (ref "R1") (pin "2") (pinfunction "2_2") (pintype "passive"))
      (node (ref "XF1") (pin "2") (pinfunction "2_2") (pintype "passive"))
    )
    (net (code "48") (name "N") (class "Default")
      (node (ref "C10") (pin "1") (pinfunction "1_1") (pintype "passive"))
      (node (ref "C12") (pin "1") (pinfunction "1_1") (pintype "passive"))
      (node (ref "IC1") (pin "2") (pinfunction "IN-_2") (pintype "passive"))
      (node (ref "J1") (pin "2") (pinfunction "2_2") (pintype "passive"))
      (node (ref "M1") (pin "2") (pinfunction "~_2") (pintype "passive"))
      (node (ref "R3") (pin "1") (pinfunction "1_1") (pintype "passive"))
      (node (ref "RV1") (pin "1") (pinfunction "1_1") (pintype "passive"))
    )
    (net (code "49") (name "Net-(IC1-VOUT)") (class "Default")
      (node (ref "IC1") (pin "6") (pinfunction "VOUT_6") (pintype "passive"))
      (node (ref "R9") (pin "1") (pinfunction "1_1") (pintype "passive"))
    )
    (net (code "50") (name "Net-(IC2-DCDC_IN)") (class "Default")
      (node (ref "C7") (pin "2") (pinfunction "2_2") (pintype "passive"))
      (node (ref "IC2") (pin "13") (pinfunction "LDO_OUT_13") (pintype "passive"))
      (node (ref "IC2") (pin "16") (pinfunction "DCDC_IN_16") (pintype "passive"))
    )
    (net (code "51") (name "Net-(IC2-DCDC_OUT)") (class "Default")
      (node (ref "C2") (pin "2") (pinfunction "2_2") (pintype "passive"))
      (node (ref "C3") (pin "1") (pinfunction "1_1") (pintype "passive"))
      (node (ref "IC2") (pin "1") (pinfunction "DCDC_OUT_1") (pintype "passive"))
      (node (ref "IC2") (pin "3") (pinfunction "HLDO_IN_3") (pintype "passive"))
    )
    (net (code "52") (name "Net-(IC2-HLDO_OUT)") (class "Default")
      (node (ref "C5") (pin "2") (pinfunction "2_2") (pintype "passive"))
      (node (ref "C6") (pin "1") (pinfunction "1_1") (pintype "passive"))
      (node (ref "IC2") (pin "5") (pinfunction "HLDO_OUT_5") (pintype "passive"))
    )
    (net (code "53") (name "Net-(IC2-INN)") (class "Default")
      (node (ref "C1") (pin "2") (pinfunction "2_2") (pintype "passive"))
      (node (ref "FB2") (pin "2") (pinfunction "2_2") (pintype "passive"))
      (node (ref "IC2") (pin "7") (pinfunction "INN_7") (pintype "passive"))
    )
    (net (code "54") (name "Net-(IC2-INP)") (class "Default")
      (node (ref "C1") (pin "1") (pinfunction "1_1") (pintype "passive"))
      (node (ref "FB1") (pin "2") (pinfunction "2_2") (pintype "passive"))
      (node (ref "IC2") (pin "6") (pinfunction "INP_6") (pintype "passive"))
    )
    (net (code "55") (name "Net-(IC2-OUTN)") (class "Default")
      (node (ref "IC2") (pin "10") (pinfunction "OUTN_10") (pintype "passive"))
      (node (ref "R11") (pin "1") (pinfunction "1_1") (pintype "passive"))
    )
    (net (code "56") (name "Net-(IC2-OUTP)") (class "Default")
      (node (ref "IC2") (pin "11") (pinfunction "OUTP_11") (pintype "passive"))
      (node (ref "R10") (pin "1") (pinfunction "1_1") (pintype "passive"))
    )
    (net (code "57") (name "Net-(MOD1-BOOT_EN)") (class "Default")
      (node (ref "MOD1") (pin "11") (pinfunction "BOOT_EN_11") (pintype "passive"))
      (node (ref "P10") (pin "1") (pinfunction "1_1") (pintype "passive"))
    )
    (net (code "58") (name "Nout") (class "Default")
      (node (ref "IC1") (pin "1") (pinfunction "IN+_1") (pintype "passive"))
      (node (ref "J1") (pin "1") (pinfunction "1_1") (pintype "passive"))
    )
    (net (code "59") (name "PE") (class "Default")
      (node (ref "D1") (pin "1") (pinfunction "1_1") (pintype "passive"))
      (node (ref "J1") (pin "5") (pinfunction "5_5") (pintype "passive"))
      (node (ref "J1") (pin "6") (pinfunction "6_6") (pintype "passive"))
      (node (ref "R5") (pin "1") (pinfunction "1_1") (pintype "passive"))
    )
    (net (code "60") (name "unconnected-(IC1-NC_1-Pad3)") (class "Default")
      (node (ref "IC1") (pin "3") (pinfunction "NC_1_3") (pintype "passive"))
    )
    (net (code "61") (name "unconnected-(IC1-NC_2-Pad5)") (class "Default")
      (node (ref "IC1") (pin "5") (pinfunction "NC_2_5") (pintype "passive"))
    )
    (net (code "62") (name "unconnected-(IC1-NC_3-Pad7)") (class "Default")
      (node (ref "IC1") (pin "7") (pinfunction "NC_3_7") (pintype "passive"))
    )
    (net (code "63") (name "unconnected-(IC1-NC_4-Pad8)") (class "Default")
      (node (ref "IC1") (pin "8") (pinfunction "NC_4_8") (pintype "passive"))
    )
    (net (code "64") (name "unconnected-(IC1-NC_5-Pad10)") (class "Default")
      (node (ref "IC1") (pin "10") (pinfunction "NC_5_10") (pintype "passive"))
    )
    (net (code "65") (name "unconnected-(MOD1-RESERVED-Pad1)") (class "Default")
      (node (ref "MOD1") (pin "1") (pinfunction "RESERVED_1") (pintype "passive+no_connect"))
    )
    (net (code "66") (name "unconnected-(MOD1-RESERVED-Pad2)") (class "Default")
      (node (ref "MOD1") (pin "2") (pinfunction "RESERVED_2") (pintype "passive+no_connect"))
    )
    (net (code "67") (name "unconnected-(MOD1-RESERVED-Pad12)") (class "Default")
      (node (ref "MOD1") (pin "12") (pinfunction "RESERVED_12") (pintype "passive+no_connect"))
    )
    (net (code "68") (name "unconnected-(MOD1-RESERVED-Pad16)") (class "Default")
      (node (ref "MOD1") (pin "16") (pinfunction "RESERVED_16") (pintype "passive+no_connect"))
    )
    (net (code "69") (name "unconnected-(P8-Pad6)") (class "Default")
      (node (ref "P8") (pin "6") (pinfunction "6_6") (pintype "passive"))
    )
    (net (code "70") (name "unconnected-(P8-Pad10)") (class "Default")
      (node (ref "P8") (pin "10") (pinfunction "10_10") (pintype "passive"))
    )
    (net (code "71") (name "unconnected-(P8-Pad12)") (class "Default")
      (node (ref "P8") (pin "12") (pinfunction "12_12") (pintype "passive"))
    )
    (net (code "72") (name "unconnected-(P8-Pad13)") (class "Default")
      (node (ref "P8") (pin "13") (pinfunction "13_13") (pintype "passive"))
    )
    (net (code "73") (name "unconnected-(P8-Pad14)") (class "Default")
      (node (ref "P8") (pin "14") (pinfunction "14_14") (pintype "passive"))
    )
    (net (code "74") (name "unconnected-(U2-P2.0{slash}TA1.0{slash}CLKIN-Pad25)") (class "Default")
      (node (ref "U2") (pin "25") (pinfunction "P2.0/TA1.0/CLKIN_25") (pintype "bidirectional"))
    )
    (net (code "75") (name "unconnected-(U2-P2.6{slash}TA0.1-Pad31)") (class "Default")
      (node (ref "U2") (pin "31") (pinfunction "P2.6/TA0.1_31") (pintype "bidirectional"))
    )
  )
)
